# mic_preamp.net
KiCad netlist of a schematic drawn in EAGLE
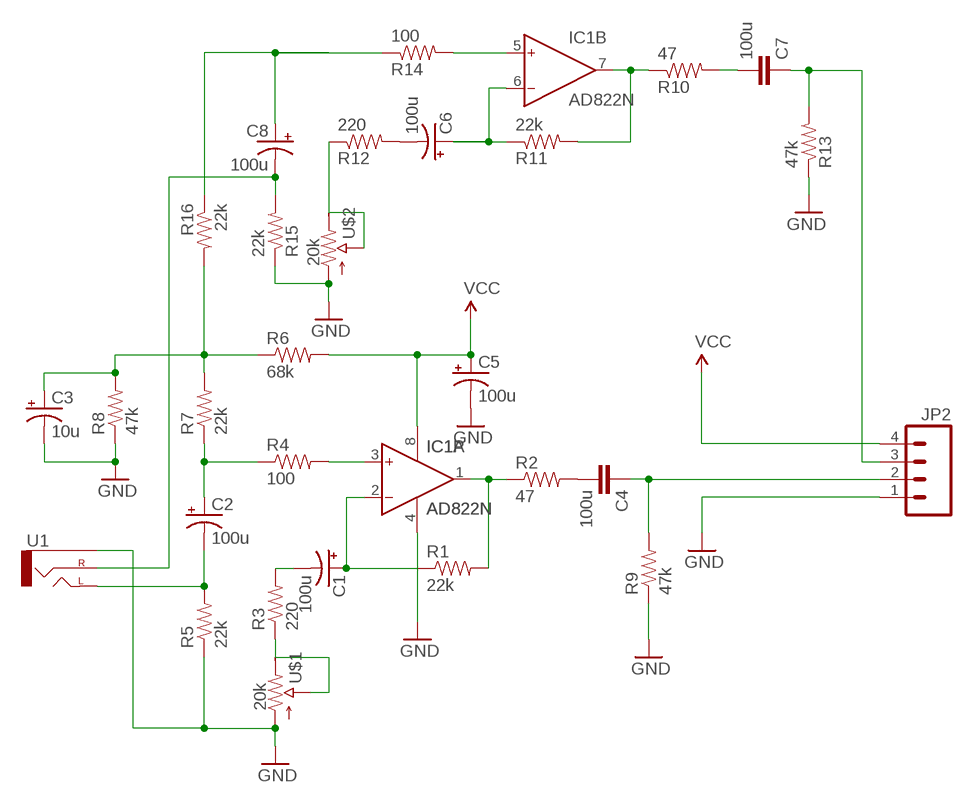
[diagram p0: schematic, sheet 1]

(export (version "E")
  (design (tool "Eeschema 10.0.6"))
  (components
    (comp (ref "C1")
      (value "100u")
      (footprint "eagle-import:CPOL-RADIAL-100UF-25V")
      (libsource (lib "eagle-import") (part "CAP_POLPTH1"))
    )
    (comp (ref "C2")
      (value "100u")
      (footprint "eagle-import:CPOL-RADIAL-100UF-25V")
      (libsource (lib "eagle-import") (part "CAP_POLPTH1"))
    )
    (comp (ref "C3")
      (value "10u")
      (footprint "eagle-import:CPOL-RADIAL-100UF-25V")
      (libsource (lib "eagle-import") (part "CAP_POLPTH1"))
    )
    (comp (ref "C4")
      (value "100u")
      (footprint "eagle-import:C2.5-4")
      (libsource (lib "eagle-import") (part "C2.5/4"))
    )
    (comp (ref "C5")
      (value "100u")
      (footprint "eagle-import:CPOL-RADIAL-100UF-25V")
      (libsource (lib "eagle-import") (part "CAP_POLPTH1"))
    )
    (comp (ref "C6")
      (value "100u")
      (footprint "eagle-import:CPOL-RADIAL-100UF-25V")
      (libsource (lib "eagle-import") (part "CAP_POLPTH1"))
    )
    (comp (ref "C7")
      (value "100u")
      (footprint "eagle-import:C2.5-4")
      (libsource (lib "eagle-import") (part "C2.5/4"))
    )
    (comp (ref "C8")
      (value "100u")
      (footprint "eagle-import:CPOL-RADIAL-100UF-25V")
      (libsource (lib "eagle-import") (part "CAP_POLPTH1"))
    )
    (comp (ref "IC1")
      (value "AD822N")
      (footprint "eagle-import:DIL08")
      (libsource (lib "eagle-import") (part "AD822N"))
    )
    (comp (ref "JP2")
      (value "M04POLAR")
      (footprint "eagle-import:MOLEX-1X4")
      (libsource (lib "eagle-import") (part "M04POLAR"))
    )
    (comp (ref "R1")
      (value "22k")
      (footprint "eagle-import:1_6W-RES")
      (libsource (lib "eagle-import") (part "RESISTORPTH-1/6W"))
    )
    (comp (ref "R2")
      (value "47")
      (footprint "eagle-import:1_6W-RES")
      (libsource (lib "eagle-import") (part "RESISTORPTH-1/6W"))
    )
    (comp (ref "R3")
      (value "220")
      (footprint "eagle-import:1_6W-RES")
      (libsource (lib "eagle-import") (part "RESISTORPTH-1/6W"))
    )
    (comp (ref "R4")
      (value "100")
      (footprint "eagle-import:1_6W-RES")
      (libsource (lib "eagle-import") (part "RESISTORPTH-1/6W"))
    )
    (comp (ref "R5")
      (value "22k")
      (footprint "eagle-import:1_6W-RES")
      (libsource (lib "eagle-import") (part "RESISTORPTH-1/6W"))
    )
    (comp (ref "R6")
      (value "68k")
      (footprint "eagle-import:1_6W-RES")
      (libsource (lib "eagle-import") (part "RESISTORPTH-1/6W"))
    )
    (comp (ref "R7")
      (value "22k")
      (footprint "eagle-import:AXIAL-0.3")
      (libsource (lib "eagle-import") (part "RESISTORAXIAL-0.3"))
    )
    (comp (ref "R8")
      (value "47k")
      (footprint "eagle-import:1_6W-RES")
      (libsource (lib "eagle-import") (part "RESISTORPTH-1/6W"))
    )
    (comp (ref "R9")
      (value "47k")
      (footprint "eagle-import:1_6W-RES")
      (libsource (lib "eagle-import") (part "RESISTORPTH-1/6W"))
    )
    (comp (ref "R10")
      (value "47")
      (footprint "eagle-import:1_6W-RES")
      (libsource (lib "eagle-import") (part "RESISTORPTH-1/6W"))
    )
    (comp (ref "R11")
      (value "22k")
      (footprint "eagle-import:1_6W-RES")
      (libsource (lib "eagle-import") (part "RESISTORPTH-1/6W"))
    )
    (comp (ref "R12")
      (value "220")
      (footprint "eagle-import:1_6W-RES")
      (libsource (lib "eagle-import") (part "RESISTORPTH-1/6W"))
    )
    (comp (ref "R13")
      (value "47k")
      (footprint "eagle-import:1_6W-RES")
      (libsource (lib "eagle-import") (part "RESISTORPTH-1/6W"))
    )
    (comp (ref "R14")
      (value "100")
      (footprint "eagle-import:1_6W-RES")
      (libsource (lib "eagle-import") (part "RESISTORPTH-1/6W"))
    )
    (comp (ref "R15")
      (value "22k")
      (footprint "eagle-import:1_6W-RES")
      (libsource (lib "eagle-import") (part "RESISTORPTH-1/6W"))
    )
    (comp (ref "R16")
      (value "22k")
      (footprint "eagle-import:AXIAL-0.3")
      (libsource (lib "eagle-import") (part "RESISTORAXIAL-0.3"))
    )
    (comp (ref "U$1")
      (value "20k")
      (footprint "eagle-import:POT_ALPHA_RV16AF-20")
      (libsource (lib "eagle-import") (part "POT-RV16AF-20"))
    )
    (comp (ref "U$2")
      (value "20k")
      (footprint "eagle-import:POT_ALPHA_RV16AF-20")
      (libsource (lib "eagle-import") (part "POT-RV16AF-20"))
    )
    (comp (ref "U1")
      (value "AUDIO-JACKPTH")
      (footprint "eagle-import:AUDIO-JACK")
      (libsource (lib "eagle-import") (part "AUDIO-JACKPTH"))
    )
  )
  (nets
    (net (code "1") (name "GND") (class "Default")
      (node (ref "C3") (pin "2") (pinfunction "-_2") (pintype "passive"))
      (node (ref "C5") (pin "2") (pinfunction "-_2") (pintype "passive"))
      (node (ref "IC1") (pin "4") (pinfunction "V-_4") (pintype "power_in"))
      (node (ref "JP2") (pin "1") (pinfunction "1_1") (pintype "passive"))
      (node (ref "R13") (pin "1") (pinfunction "1_1") (pintype "passive"))
      (node (ref "R15") (pin "1") (pinfunction "1_1") (pintype "passive"))
      (node (ref "R5") (pin "1") (pinfunction "1_1") (pintype "passive"))
      (node (ref "R8") (pin "1") (pinfunction "1_1") (pintype "passive"))
      (node (ref "R9") (pin "1") (pinfunction "1_1") (pintype "passive"))
      (node (ref "U$1") (pin "1") (pinfunction "A_1") (pintype "passive"))
      (node (ref "U$2") (pin "1") (pinfunction "A_1") (pintype "passive"))
      (node (ref "U1") (pin "SLEEVE") (pinfunction "SLEEVE_SLEEVE") (pintype "bidirectional"))
    )
    (net (code "2") (name "Net-(C1-+)") (class "Default")
      (node (ref "C1") (pin "1") (pinfunction "+_1") (pintype "passive"))
      (node (ref "IC1") (pin "2") (pinfunction "IN-_2") (pintype "input"))
      (node (ref "R1") (pin "1") (pinfunction "1_1") (pintype "passive"))
    )
    (net (code "3") (name "Net-(C1--)") (class "Default")
      (node (ref "C1") (pin "2") (pinfunction "-_2") (pintype "passive"))
      (node (ref "R3") (pin "2") (pinfunction "2_2") (pintype "passive"))
    )
    (net (code "4") (name "Net-(C2-+)") (class "Default")
      (node (ref "C2") (pin "1") (pinfunction "+_1") (pintype "passive"))
      (node (ref "R4") (pin "1") (pinfunction "1_1") (pintype "passive"))
      (node (ref "R7") (pin "P$1") (pinfunction "1_P$1") (pintype "passive"))
    )
    (net (code "5") (name "Net-(C2--)") (class "Default")
      (node (ref "C2") (pin "2") (pinfunction "-_2") (pintype "passive"))
      (node (ref "R5") (pin "2") (pinfunction "2_2") (pintype "passive"))
      (node (ref "U1") (pin "TIP") (pinfunction "LEFT_TIP") (pintype "bidirectional"))
    )
    (net (code "6") (name "Net-(C3-+)") (class "Default")
      (node (ref "C3") (pin "1") (pinfunction "+_1") (pintype "passive"))
      (node (ref "R16") (pin "P$2") (pinfunction "2_P$2") (pintype "passive"))
      (node (ref "R6") (pin "1") (pinfunction "1_1") (pintype "passive"))
      (node (ref "R7") (pin "P$2") (pinfunction "2_P$2") (pintype "passive"))
      (node (ref "R8") (pin "2") (pinfunction "2_2") (pintype "passive"))
    )
    (net (code "7") (name "Net-(C4-Pad1)") (class "Default")
      (node (ref "C4") (pin "1") (pinfunction "1_1") (pintype "passive"))
      (node (ref "JP2") (pin "2") (pinfunction "2_2") (pintype "passive"))
      (node (ref "R9") (pin "2") (pinfunction "2_2") (pintype "passive"))
    )
    (net (code "8") (name "Net-(C4-Pad2)") (class "Default")
      (node (ref "C4") (pin "2") (pinfunction "2_2") (pintype "passive"))
      (node (ref "R2") (pin "2") (pinfunction "2_2") (pintype "passive"))
    )
    (net (code "9") (name "Net-(C6-+)") (class "Default")
      (node (ref "C6") (pin "1") (pinfunction "+_1") (pintype "passive"))
      (node (ref "IC1") (pin "6") (pinfunction "IN-_6") (pintype "input"))
      (node (ref "R11") (pin "1") (pinfunction "1_1") (pintype "passive"))
    )
    (net (code "10") (name "Net-(C6--)") (class "Default")
      (node (ref "C6") (pin "2") (pinfunction "-_2") (pintype "passive"))
      (node (ref "R12") (pin "2") (pinfunction "2_2") (pintype "passive"))
    )
    (net (code "11") (name "Net-(C7-Pad1)") (class "Default")
      (node (ref "C7") (pin "1") (pinfunction "1_1") (pintype "passive"))
      (node (ref "JP2") (pin "3") (pinfunction "3_3") (pintype "passive"))
      (node (ref "R13") (pin "2") (pinfunction "2_2") (pintype "passive"))
    )
    (net (code "12") (name "Net-(C7-Pad2)") (class "Default")
      (node (ref "C7") (pin "2") (pinfunction "2_2") (pintype "passive"))
      (node (ref "R10") (pin "2") (pinfunction "2_2") (pintype "passive"))
    )
    (net (code "13") (name "Net-(C8-+)") (class "Default")
      (node (ref "C8") (pin "1") (pinfunction "+_1") (pintype "passive"))
      (node (ref "R14") (pin "1") (pinfunction "1_1") (pintype "passive"))
      (node (ref "R16") (pin "P$1") (pinfunction "1_P$1") (pintype "passive"))
    )
    (net (code "14") (name "Net-(C8--)") (class "Default")
      (node (ref "C8") (pin "2") (pinfunction "-_2") (pintype "passive"))
      (node (ref "R15") (pin "2") (pinfunction "2_2") (pintype "passive"))
      (node (ref "U1") (pin "RING") (pinfunction "RIGHT_RING") (pintype "bidirectional"))
    )
    (net (code "15") (name "Net-(IC1A-IN+)") (class "Default")
      (node (ref "IC1") (pin "3") (pinfunction "IN+_3") (pintype "input"))
      (node (ref "R4") (pin "2") (pinfunction "2_2") (pintype "passive"))
    )
    (net (code "16") (name "Net-(IC1A-OUT)") (class "Default")
      (node (ref "IC1") (pin "1") (pinfunction "OUT_1") (pintype "output"))
      (node (ref "R1") (pin "2") (pinfunction "2_2") (pintype "passive"))
      (node (ref "R2") (pin "1") (pinfunction "1_1") (pintype "passive"))
    )
    (net (code "17") (name "Net-(IC1B-IN+)") (class "Default")
      (node (ref "IC1") (pin "5") (pinfunction "IN+_5") (pintype "input"))
      (node (ref "R14") (pin "2") (pinfunction "2_2") (pintype "passive"))
    )
    (net (code "18") (name "Net-(IC1B-OUT)") (class "Default")
      (node (ref "IC1") (pin "7") (pinfunction "OUT_7") (pintype "output"))
      (node (ref "R10") (pin "1") (pinfunction "1_1") (pintype "passive"))
      (node (ref "R11") (pin "2") (pinfunction "2_2") (pintype "passive"))
    )
    (net (code "19") (name "Net-(U$1-E)") (class "Default")
      (node (ref "R3") (pin "1") (pinfunction "1_1") (pintype "passive"))
      (node (ref "U$1") (pin "2") (pinfunction "S_2") (pintype "passive"))
      (node (ref "U$1") (pin "3") (pinfunction "E_3") (pintype "passive"))
    )
    (net (code "20") (name "Net-(U$2-E)") (class "Default")
      (node (ref "R12") (pin "1") (pinfunction "1_1") (pintype "passive"))
      (node (ref "U$2") (pin "2") (pinfunction "S_2") (pintype "passive"))
      (node (ref "U$2") (pin "3") (pinfunction "E_3") (pintype "passive"))
    )
    (net (code "21") (name "VCC") (class "Default")
      (node (ref "C5") (pin "1") (pinfunction "+_1") (pintype "passive"))
      (node (ref "IC1") (pin "8") (pinfunction "V+_8") (pintype "power_in"))
      (node (ref "JP2") (pin "4") (pinfunction "4_4") (pintype "passive"))
      (node (ref "R6") (pin "2") (pinfunction "2_2") (pintype "passive"))
    )
  )
)
